# Earphone-3.net
KiCad netlist of a schematic drawn in Altium Designer
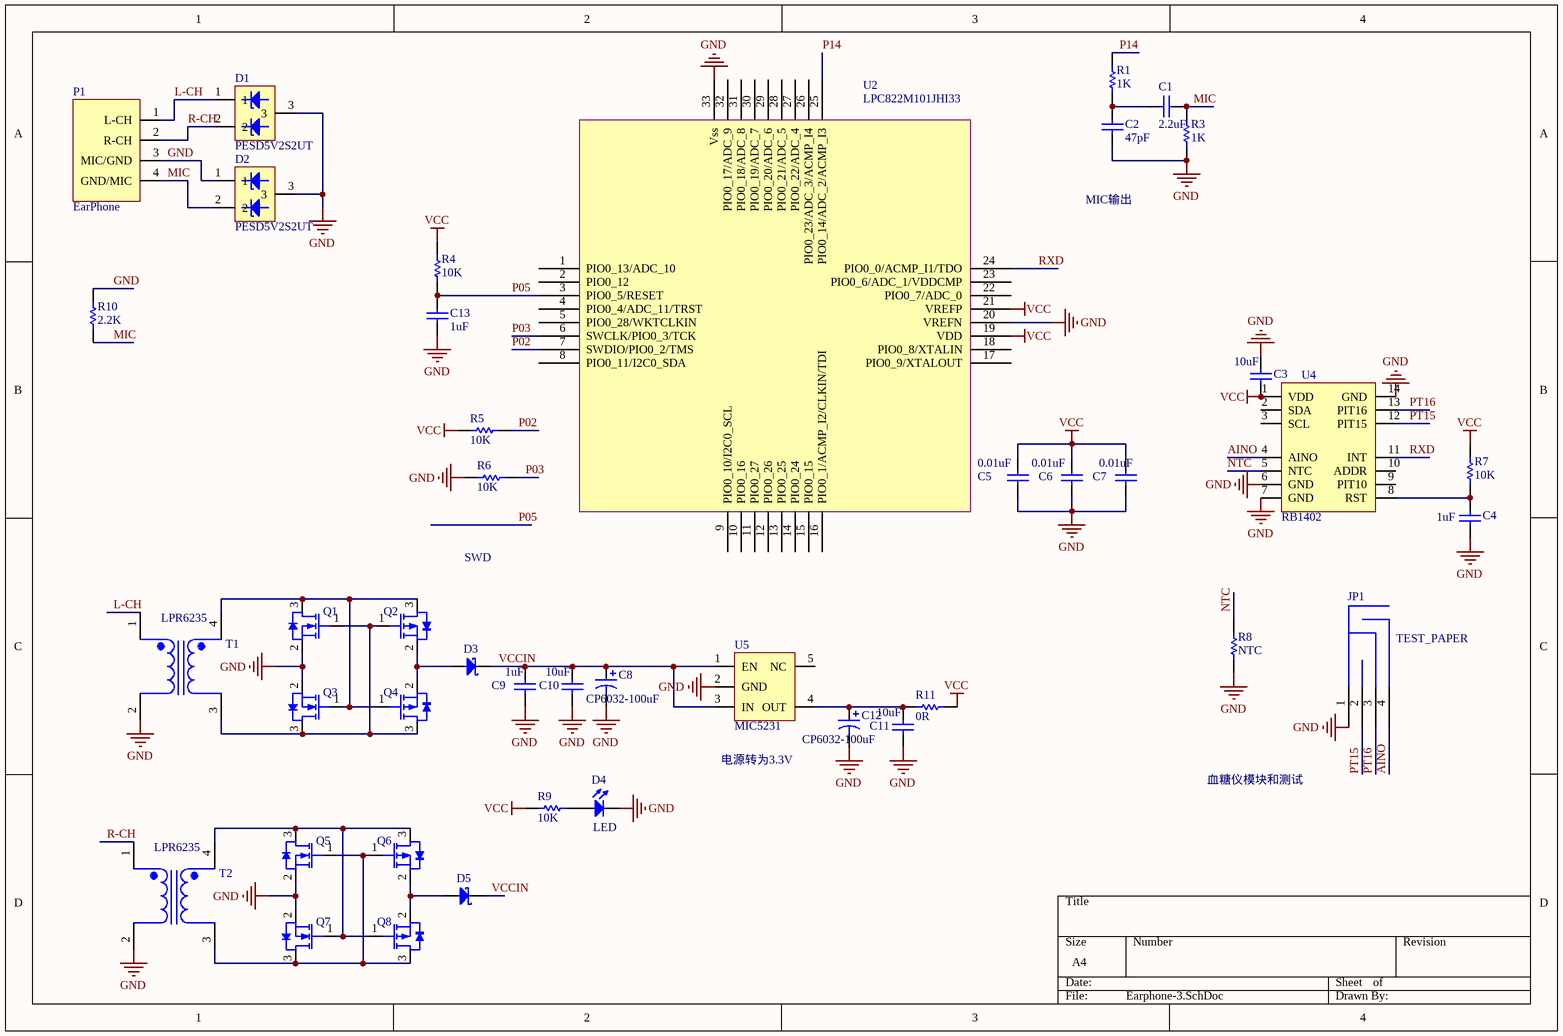
[diagram p0: Earphone-3.SchDoc]

(export (version "E")
  (design (tool "Eeschema 10.0.6"))
  (components
    (comp (ref "C1") (value "2.2uF") (footprint "0402C") (libsource (lib "Schlib1") (part "CAP")))
    (comp (ref "C2") (value "47pF") (footprint "0402C") (libsource (lib "Schlib1") (part "CAP")))
    (comp (ref "C3") (value "10uF") (footprint "0402C") (libsource (lib "Schlib1") (part "CAP")))
    (comp (ref "C4") (value "1uF") (footprint "0402C") (libsource (lib "Schlib1") (part "CAP")))
    (comp (ref "C5") (value "0.01uF") (footprint "0402C") (libsource (lib "Schlib1") (part "CAP")))
    (comp (ref "C6") (value "0.01uF") (footprint "0402C") (libsource (lib "Schlib1") (part "CAP")))
    (comp (ref "C7") (value "0.01uF") (footprint "0402C") (libsource (lib "Schlib1") (part "CAP")))
    (comp (ref "C8")
      (value "CP6032-100uF")
      (footprint "T3216-18[A]")
      (libsource (lib "Schlib1") (part "CAP POL2"))
    )
    (comp (ref "C9") (value "1uF") (footprint "0402C") (libsource (lib "Schlib1") (part "CAP")))
    (comp (ref "C10") (value "10uF") (footprint "0402C") (libsource (lib "Schlib1") (part "CAP")))
    (comp (ref "C11") (value "10uF") (footprint "0402C") (libsource (lib "Schlib1") (part "CAP")))
    (comp (ref "C12")
      (value "CP6032-100uF")
      (footprint "T3216-18[A]")
      (libsource (lib "Schlib1") (part "CAP POL2"))
    )
    (comp (ref "C13") (value "1uF") (footprint "0402C") (libsource (lib "Schlib1") (part "CAP")))
    (comp (ref "D1")
      (value "PESD5V2S2UT")
      (footprint "SOT23")
      (description "SOT23")
      (libsource (lib "Schlib1") (part "PESD5V2S2UT"))
    )
    (comp (ref "D2")
      (value "PESD5V2S2UT")
      (footprint "SOT23")
      (description "SOT23")
      (libsource (lib "Schlib1") (part "PESD5V2S2UT"))
    )
    (comp (ref "D3")
      (value "PMEG4002EJ")
      (footprint "SOD323")
      (description "SOD323F")
      (libsource (lib "Schlib1") (part "PMEG4002EJ"))
    )
    (comp (ref "D4") (value "LED") (footprint "0603L") (libsource (lib "Schlib1") (part "LED")))
    (comp (ref "D5")
      (value "PMEG4002EJ")
      (footprint "SOD323")
      (description "SOD323F")
      (libsource (lib "Schlib1") (part "PMEG4002EJ"))
    )
    (comp (ref "JP1")
      (value "TEST_PAPER")
      (footprint "TEST_PAPER")
      (libsource (lib "Schlib1") (part "TEST_PAPER"))
    )
    (comp (ref "P1") (value "EarPhone") (footprint "USB-A") (libsource (lib "Schlib1") (part "EarPhone")))
    (comp (ref "Q1")
      (value "N-MOSFET")
      (footprint "SOT23")
      (description "4N80 N-Channel MOSFET")
      (libsource (lib "Schlib1") (part "N-MOSFET"))
    )
    (comp (ref "Q2")
      (value "P-MOSFET")
      (footprint "SOT23")
      (description "P-Channel MOSFET")
      (libsource (lib "Schlib1") (part "P-MOSFET"))
    )
    (comp (ref "Q3")
      (value "N-MOSFET")
      (footprint "SOT23")
      (description "4N80 N-Channel MOSFET")
      (libsource (lib "Schlib1") (part "N-MOSFET"))
    )
    (comp (ref "Q4")
      (value "P-MOSFET")
      (footprint "SOT23")
      (description "P-Channel MOSFET")
      (libsource (lib "") (part "P-MOSFET_1"))
    )
    (comp (ref "Q5")
      (value "N-MOSFET")
      (footprint "SOT23")
      (description "4N80 N-Channel MOSFET")
      (libsource (lib "Schlib1") (part "N-MOSFET"))
    )
    (comp (ref "Q6")
      (value "P-MOSFET")
      (footprint "SOT23")
      (description "P-Channel MOSFET")
      (libsource (lib "Schlib1") (part "P-MOSFET"))
    )
    (comp (ref "Q7")
      (value "N-MOSFET")
      (footprint "SOT23")
      (description "4N80 N-Channel MOSFET")
      (libsource (lib "Schlib1") (part "N-MOSFET"))
    )
    (comp (ref "Q8")
      (value "P-MOSFET")
      (footprint "SOT23")
      (description "P-Channel MOSFET")
      (libsource (lib "") (part "P-MOSFET_1"))
    )
    (comp (ref "R1") (value "1K") (footprint "0402R") (libsource (lib "Schlib1") (part "RES")))
    (comp (ref "R3") (value "1K") (footprint "0402R") (libsource (lib "Schlib1") (part "RES")))
    (comp (ref "R4") (value "10K") (footprint "0402R") (libsource (lib "Schlib1") (part "RES")))
    (comp (ref "R5") (value "10K") (footprint "0402R") (libsource (lib "Schlib1") (part "RES")))
    (comp (ref "R6") (value "10K") (footprint "0402R") (libsource (lib "Schlib1") (part "RES")))
    (comp (ref "R7") (value "10K") (footprint "0402R") (libsource (lib "Schlib1") (part "RES")))
    (comp (ref "R8") (value "NTC") (footprint "0603R") (libsource (lib "Schlib1") (part "RES")))
    (comp (ref "R9") (value "10K") (footprint "0402R") (libsource (lib "Schlib1") (part "RES")))
    (comp (ref "R10") (value "2.2K") (footprint "0402R") (libsource (lib "Schlib1") (part "RES")))
    (comp (ref "R11") (value "0R") (footprint "0402R") (libsource (lib "Schlib1") (part "RES")))
    (comp (ref "T1") (value "LPR6235") (footprint "Trans EMI") (libsource (lib "Schlib1") (part "Trans EMI")))
    (comp (ref "T2") (value "LPR6235") (footprint "Trans EMI") (libsource (lib "Schlib1") (part "Trans EMI")))
    (comp (ref "U2")
      (value "LPC822M101JHI33")
      (footprint "QFN50P500X500X100-33N")
      (libsource (lib "Schlib1") (part "LPC822M101JHI33"))
    )
    (comp (ref "U4") (value "RB1402") (footprint "RB1402") (libsource (lib "Schlib1") (part "RB1402")))
    (comp (ref "U5") (value "MIC5231") (footprint "SOT23-5") (libsource (lib "Schlib1") (part "MIC5231")))
  )
  (nets
    (net (code "1") (name "/AINO") (class "Default")
      (node (ref "JP1") (pin "4") (pinfunction "P_4") (pintype "passive"))
      (node (ref "U4") (pin "4") (pinfunction "AINO_4") (pintype "passive"))
    )
    (net (code "2") (name "/L-CH") (class "Default")
      (node (ref "D1") (pin "1") (pinfunction "1_1") (pintype "passive"))
      (node (ref "P1") (pin "1") (pinfunction "L-CH_1") (pintype "passive"))
      (node (ref "T1") (pin "1") (pinfunction "1_1") (pintype "passive"))
    )
    (net (code "3") (name "/MIC") (class "Default")
      (node (ref "C1") (pin "1") (pinfunction "1_1") (pintype "passive"))
      (node (ref "D2") (pin "2") (pinfunction "2_2") (pintype "passive"))
      (node (ref "P1") (pin "4") (pinfunction "GND/MIC_4") (pintype "passive"))
      (node (ref "R10") (pin "1") (pinfunction "1_1") (pintype "passive"))
      (node (ref "R3") (pin "1") (pinfunction "1_1") (pintype "passive"))
    )
    (net (code "4") (name "/NTC") (class "Default")
      (node (ref "R8") (pin "2") (pinfunction "2_2") (pintype "passive"))
      (node (ref "U4") (pin "5") (pinfunction "NTC_5") (pintype "passive"))
    )
    (net (code "5") (name "/P02") (class "Default")
      (node (ref "R5") (pin "2") (pinfunction "2_2") (pintype "passive"))
      (node (ref "U2") (pin "7") (pinfunction "SWDIO/PIO0_2/TMS_7") (pintype "passive"))
    )
    (net (code "6") (name "/P03") (class "Default")
      (node (ref "R6") (pin "1") (pinfunction "1_1") (pintype "passive"))
      (node (ref "U2") (pin "6") (pinfunction "SWCLK/PIO0_3/TCK_6") (pintype "passive"))
    )
    (net (code "7") (name "/P05") (class "Default")
      (node (ref "C13") (pin "2") (pinfunction "2_2") (pintype "passive"))
      (node (ref "R4") (pin "1") (pinfunction "1_1") (pintype "passive"))
      (node (ref "U2") (pin "3") (pinfunction "PIO0_5/RESET_3") (pintype "passive"))
    )
    (net (code "8") (name "/P14") (class "Default")
      (node (ref "R1") (pin "1") (pinfunction "1_1") (pintype "passive"))
      (node (ref "U2") (pin "25") (pinfunction "PIO0_14/ADC_2/ACMP_I3_25") (pintype "passive"))
    )
    (net (code "9") (name "/PT15") (class "Default")
      (node (ref "JP1") (pin "2") (pinfunction "PC10_2") (pintype "passive"))
      (node (ref "U4") (pin "12") (pinfunction "PIT15_12") (pintype "passive"))
    )
    (net (code "10") (name "/PT16") (class "Default")
      (node (ref "JP1") (pin "3") (pinfunction "NOP_3") (pintype "passive"))
      (node (ref "U4") (pin "13") (pinfunction "PIT16_13") (pintype "passive"))
    )
    (net (code "11") (name "/R-CH") (class "Default")
      (node (ref "D1") (pin "2") (pinfunction "2_2") (pintype "passive"))
      (node (ref "P1") (pin "2") (pinfunction "R-CH_2") (pintype "passive"))
      (node (ref "T2") (pin "1") (pinfunction "1_1") (pintype "passive"))
    )
    (net (code "12") (name "/RXD") (class "Default")
      (node (ref "U2") (pin "24") (pinfunction "PIO0_0/ACMP_I1/TDO_24") (pintype "passive"))
      (node (ref "U4") (pin "11") (pinfunction "INT_11") (pintype "passive"))
    )
    (net (code "13") (name "/VCCIN") (class "Default")
      (node (ref "C10") (pin "2") (pinfunction "2_2") (pintype "passive"))
      (node (ref "C8") (pin "1") (pinfunction "1_1") (pintype "passive"))
      (node (ref "C9") (pin "2") (pinfunction "2_2") (pintype "passive"))
      (node (ref "D3") (pin "1") (pinfunction "1_1") (pintype "passive"))
      (node (ref "D5") (pin "1") (pinfunction "1_1") (pintype "passive"))
      (node (ref "U5") (pin "1") (pinfunction "EN_1") (pintype "passive"))
      (node (ref "U5") (pin "3") (pinfunction "IN_3") (pintype "passive"))
    )
    (net (code "14") (name "GND") (class "Default")
      (node (ref "C10") (pin "1") (pinfunction "1_1") (pintype "passive"))
      (node (ref "C11") (pin "1") (pinfunction "1_1") (pintype "passive"))
      (node (ref "C12") (pin "2") (pinfunction "2_2") (pintype "passive"))
      (node (ref "C13") (pin "1") (pinfunction "1_1") (pintype "passive"))
      (node (ref "C2") (pin "1") (pinfunction "1_1") (pintype "passive"))
      (node (ref "C3") (pin "2") (pinfunction "2_2") (pintype "passive"))
      (node (ref "C4") (pin "1") (pinfunction "1_1") (pintype "passive"))
      (node (ref "C5") (pin "1") (pinfunction "1_1") (pintype "passive"))
      (node (ref "C6") (pin "1") (pinfunction "1_1") (pintype "passive"))
      (node (ref "C7") (pin "1") (pinfunction "1_1") (pintype "passive"))
      (node (ref "C8") (pin "2") (pinfunction "2_2") (pintype "passive"))
      (node (ref "C9") (pin "1") (pinfunction "1_1") (pintype "passive"))
      (node (ref "D1") (pin "3") (pinfunction "3_3") (pintype "passive"))
      (node (ref "D2") (pin "1") (pinfunction "1_1") (pintype "passive"))
      (node (ref "D2") (pin "3") (pinfunction "3_3") (pintype "passive"))
      (node (ref "D4") (pin "2") (pinfunction "K_2") (pintype "passive"))
      (node (ref "JP1") (pin "1") (pinfunction "N_1") (pintype "passive"))
      (node (ref "P1") (pin "3") (pinfunction "MIC/GND_3") (pintype "passive"))
      (node (ref "Q1") (pin "2") (pinfunction "S_2") (pintype "passive"))
      (node (ref "Q3") (pin "2") (pinfunction "S_2") (pintype "passive"))
      (node (ref "Q5") (pin "2") (pinfunction "S_2") (pintype "passive"))
      (node (ref "Q7") (pin "2") (pinfunction "S_2") (pintype "passive"))
      (node (ref "R10") (pin "2") (pinfunction "2_2") (pintype "passive"))
      (node (ref "R3") (pin "2") (pinfunction "2_2") (pintype "passive"))
      (node (ref "R6") (pin "2") (pinfunction "2_2") (pintype "passive"))
      (node (ref "R8") (pin "1") (pinfunction "1_1") (pintype "passive"))
      (node (ref "T1") (pin "2") (pinfunction "2_2") (pintype "passive"))
      (node (ref "T2") (pin "2") (pinfunction "2_2") (pintype "passive"))
      (node (ref "U2") (pin "20") (pinfunction "VREFN_20") (pintype "passive"))
      (node (ref "U2") (pin "33") (pinfunction "Vss_33") (pintype "passive"))
      (node (ref "U4") (pin "14") (pinfunction "GND_14") (pintype "passive"))
      (node (ref "U4") (pin "6") (pinfunction "GND_6") (pintype "passive"))
      (node (ref "U4") (pin "7") (pinfunction "GND_7") (pintype "passive"))
      (node (ref "U5") (pin "2") (pinfunction "GND_2") (pintype "passive"))
    )
    (net (code "15") (name "Net-(C1-Pad2)") (class "Default")
      (node (ref "C1") (pin "2") (pinfunction "2_2") (pintype "passive"))
      (node (ref "C2") (pin "2") (pinfunction "2_2") (pintype "passive"))
      (node (ref "R1") (pin "2") (pinfunction "2_2") (pintype "passive"))
    )
    (net (code "16") (name "Net-(D4-A)") (class "Default")
      (node (ref "D4") (pin "1") (pinfunction "A_1") (pintype "passive"))
      (node (ref "R9") (pin "2") (pinfunction "2_2") (pintype "passive"))
    )
    (net (code "17") (name "Net-(Q1-D)") (class "Default")
      (node (ref "Q1") (pin "3") (pinfunction "D_3") (pintype "passive"))
      (node (ref "Q2") (pin "3") (pinfunction "D_3") (pintype "passive"))
      (node (ref "Q3") (pin "1") (pinfunction "G_1") (pintype "passive"))
      (node (ref "Q4") (pin "1") (pinfunction "G_1") (pintype "passive"))
      (node (ref "T1") (pin "4") (pinfunction "4_4") (pintype "passive"))
    )
    (net (code "18") (name "Net-(Q1-G)") (class "Default")
      (node (ref "Q1") (pin "1") (pinfunction "G_1") (pintype "passive"))
      (node (ref "Q2") (pin "1") (pinfunction "G_1") (pintype "passive"))
      (node (ref "Q3") (pin "3") (pinfunction "D_3") (pintype "passive"))
      (node (ref "Q4") (pin "3") (pinfunction "D_3") (pintype "passive"))
      (node (ref "T1") (pin "3") (pinfunction "3_3") (pintype "passive"))
    )
    (net (code "19") (name "Net-(Q2-S)") (class "Default")
      (node (ref "D3") (pin "2") (pinfunction "2_2") (pintype "passive"))
      (node (ref "Q2") (pin "2") (pinfunction "S_2") (pintype "passive"))
      (node (ref "Q4") (pin "2") (pinfunction "S_2") (pintype "passive"))
    )
    (net (code "20") (name "Net-(Q5-D)") (class "Default")
      (node (ref "Q5") (pin "3") (pinfunction "D_3") (pintype "passive"))
      (node (ref "Q6") (pin "3") (pinfunction "D_3") (pintype "passive"))
      (node (ref "Q7") (pin "1") (pinfunction "G_1") (pintype "passive"))
      (node (ref "Q8") (pin "1") (pinfunction "G_1") (pintype "passive"))
      (node (ref "T2") (pin "4") (pinfunction "4_4") (pintype "passive"))
    )
    (net (code "21") (name "Net-(Q5-G)") (class "Default")
      (node (ref "Q5") (pin "1") (pinfunction "G_1") (pintype "passive"))
      (node (ref "Q6") (pin "1") (pinfunction "G_1") (pintype "passive"))
      (node (ref "Q7") (pin "3") (pinfunction "D_3") (pintype "passive"))
      (node (ref "Q8") (pin "3") (pinfunction "D_3") (pintype "passive"))
      (node (ref "T2") (pin "3") (pinfunction "3_3") (pintype "passive"))
    )
    (net (code "22") (name "Net-(Q6-S)") (class "Default")
      (node (ref "D5") (pin "2") (pinfunction "2_2") (pintype "passive"))
      (node (ref "Q6") (pin "2") (pinfunction "S_2") (pintype "passive"))
      (node (ref "Q8") (pin "2") (pinfunction "S_2") (pintype "passive"))
    )
    (net (code "23") (name "Net-(U4-RST)") (class "Default")
      (node (ref "C4") (pin "2") (pinfunction "2_2") (pintype "passive"))
      (node (ref "R7") (pin "1") (pinfunction "1_1") (pintype "passive"))
      (node (ref "U4") (pin "8") (pinfunction "RST_8") (pintype "passive"))
    )
    (net (code "24") (name "Net-(U5-OUT)") (class "Default")
      (node (ref "C11") (pin "2") (pinfunction "2_2") (pintype "passive"))
      (node (ref "C12") (pin "1") (pinfunction "1_1") (pintype "passive"))
      (node (ref "R11") (pin "1") (pinfunction "1_1") (pintype "passive"))
      (node (ref "U5") (pin "4") (pinfunction "OUT_4") (pintype "passive"))
    )
    (net (code "25") (name "VCC") (class "Default")
      (node (ref "C3") (pin "1") (pinfunction "1_1") (pintype "passive"))
      (node (ref "C5") (pin "2") (pinfunction "2_2") (pintype "passive"))
      (node (ref "C6") (pin "2") (pinfunction "2_2") (pintype "passive"))
      (node (ref "C7") (pin "2") (pinfunction "2_2") (pintype "passive"))
      (node (ref "R11") (pin "2") (pinfunction "2_2") (pintype "passive"))
      (node (ref "R4") (pin "2") (pinfunction "2_2") (pintype "passive"))
      (node (ref "R5") (pin "1") (pinfunction "1_1") (pintype "passive"))
      (node (ref "R7") (pin "2") (pinfunction "2_2") (pintype "passive"))
      (node (ref "R9") (pin "1") (pinfunction "1_1") (pintype "passive"))
      (node (ref "U2") (pin "19") (pinfunction "VDD_19") (pintype "passive"))
      (node (ref "U2") (pin "21") (pinfunction "VREFP_21") (pintype "passive"))
      (node (ref "U4") (pin "1") (pinfunction "VDD_1") (pintype "passive"))
    )
    (net (code "26") (name "unconnected-(U2-PIO0_1{slash}ACMP_I2{slash}CLKIN{slash}TDI-Pad16)") (class "Default")
      (node (ref "U2") (pin "16") (pinfunction "PIO0_1/ACMP_I2/CLKIN/TDI_16") (pintype "passive"))
    )
    (net (code "27") (name "unconnected-(U2-PIO0_4{slash}ADC_11{slash}TRST-Pad4)") (class "Default")
      (node (ref "U2") (pin "4") (pinfunction "PIO0_4/ADC_11/TRST_4") (pintype "passive"))
    )
    (net (code "28") (name "unconnected-(U2-PIO0_6{slash}ADC_1{slash}VDDCMP-Pad23)") (class "Default")
      (node (ref "U2") (pin "23") (pinfunction "PIO0_6/ADC_1/VDDCMP_23") (pintype "passive"))
    )
    (net (code "29") (name "unconnected-(U2-PIO0_7{slash}ADC_0-Pad22)") (class "Default")
      (node (ref "U2") (pin "22") (pinfunction "PIO0_7/ADC_0_22") (pintype "passive"))
    )
    (net (code "30") (name "unconnected-(U2-PIO0_8{slash}XTALIN-Pad18)") (class "Default")
      (node (ref "U2") (pin "18") (pinfunction "PIO0_8/XTALIN_18") (pintype "passive"))
    )
    (net (code "31") (name "unconnected-(U2-PIO0_9{slash}XTALOUT-Pad17)") (class "Default")
      (node (ref "U2") (pin "17") (pinfunction "PIO0_9/XTALOUT_17") (pintype "passive"))
    )
    (net (code "32") (name "unconnected-(U2-PIO0_10{slash}I2C0_SCL-Pad9)") (class "Default")
      (node (ref "U2") (pin "9") (pinfunction "PIO0_10/I2C0_SCL_9") (pintype "passive"))
    )
    (net (code "33") (name "unconnected-(U2-PIO0_11{slash}I2C0_SDA-Pad8)") (class "Default")
      (node (ref "U2") (pin "8") (pinfunction "PIO0_11/I2C0_SDA_8") (pintype "passive"))
    )
    (net (code "34") (name "unconnected-(U2-PIO0_12-Pad2)") (class "Default")
      (node (ref "U2") (pin "2") (pinfunction "PIO0_12_2") (pintype "passive"))
    )
    (net (code "35") (name "unconnected-(U2-PIO0_13{slash}ADC_10-Pad1)") (class "Default")
      (node (ref "U2") (pin "1") (pinfunction "PIO0_13/ADC_10_1") (pintype "passive"))
    )
    (net (code "36") (name "unconnected-(U2-PIO0_15-Pad15)") (class "Default")
      (node (ref "U2") (pin "15") (pinfunction "PIO0_15_15") (pintype "passive"))
    )
    (net (code "37") (name "unconnected-(U2-PIO0_16-Pad10)") (class "Default")
      (node (ref "U2") (pin "10") (pinfunction "PIO0_16_10") (pintype "passive"))
    )
    (net (code "38") (name "unconnected-(U2-PIO0_17{slash}ADC_9-Pad32)") (class "Default")
      (node (ref "U2") (pin "32") (pinfunction "PIO0_17/ADC_9_32") (pintype "passive"))
    )
    (net (code "39") (name "unconnected-(U2-PIO0_18{slash}ADC_8-Pad31)") (class "Default")
      (node (ref "U2") (pin "31") (pinfunction "PIO0_18/ADC_8_31") (pintype "passive"))
    )
    (net (code "40") (name "unconnected-(U2-PIO0_19{slash}ADC_7-Pad30)") (class "Default")
      (node (ref "U2") (pin "30") (pinfunction "PIO0_19/ADC_7_30") (pintype "passive"))
    )
    (net (code "41") (name "unconnected-(U2-PIO0_20{slash}ADC_6-Pad29)") (class "Default")
      (node (ref "U2") (pin "29") (pinfunction "PIO0_20/ADC_6_29") (pintype "passive"))
    )
    (net (code "42") (name "unconnected-(U2-PIO0_21{slash}ADC_5-Pad28)") (class "Default")
      (node (ref "U2") (pin "28") (pinfunction "PIO0_21/ADC_5_28") (pintype "passive"))
    )
    (net (code "43") (name "unconnected-(U2-PIO0_22{slash}ADC_4-Pad27)") (class "Default")
      (node (ref "U2") (pin "27") (pinfunction "PIO0_22/ADC_4_27") (pintype "passive"))
    )
    (net (code "44") (name "unconnected-(U2-PIO0_23{slash}ADC_3{slash}ACMP_I4-Pad26)") (class "Default")
      (node (ref "U2") (pin "26") (pinfunction "PIO0_23/ADC_3/ACMP_I4_26") (pintype "passive"))
    )
    (net (code "45") (name "unconnected-(U2-PIO0_24-Pad14)") (class "Default")
      (node (ref "U2") (pin "14") (pinfunction "PIO0_24_14") (pintype "passive"))
    )
    (net (code "46") (name "unconnected-(U2-PIO0_25-Pad13)") (class "Default")
      (node (ref "U2") (pin "13") (pinfunction "PIO0_25_13") (pintype "passive"))
    )
    (net (code "47") (name "unconnected-(U2-PIO0_26-Pad12)") (class "Default")
      (node (ref "U2") (pin "12") (pinfunction "PIO0_26_12") (pintype "passive"))
    )
    (net (code "48") (name "unconnected-(U2-PIO0_27-Pad11)") (class "Default")
      (node (ref "U2") (pin "11") (pinfunction "PIO0_27_11") (pintype "passive"))
    )
    (net (code "49") (name "unconnected-(U2-PIO0_28{slash}WKTCLKIN-Pad5)") (class "Default")
      (node (ref "U2") (pin "5") (pinfunction "PIO0_28/WKTCLKIN_5") (pintype "passive"))
    )
    (net (code "50") (name "unconnected-(U4-ADDR-Pad10)") (class "Default")
      (node (ref "U4") (pin "10") (pinfunction "ADDR_10") (pintype "passive"))
    )
    (net (code "51") (name "unconnected-(U4-PIT10-Pad9)") (class "Default")
      (node (ref "U4") (pin "9") (pinfunction "PIT10_9") (pintype "passive"))
    )
    (net (code "52") (name "unconnected-(U4-SCL-Pad3)") (class "Default")
      (node (ref "U4") (pin "3") (pinfunction "SCL_3") (pintype "passive"))
    )
    (net (code "53") (name "unconnected-(U4-SDA-Pad2)") (class "Default")
      (node (ref "U4") (pin "2") (pinfunction "SDA_2") (pintype "passive"))
    )
    (net (code "54") (name "unconnected-(U5-NC-Pad5)") (class "Default")
      (node (ref "U5") (pin "5") (pinfunction "NC_5") (pintype "passive"))
    )
  )
)
